# NFC_Card2.net
KiCad netlist of a schematic drawn in EasyEDA Pro
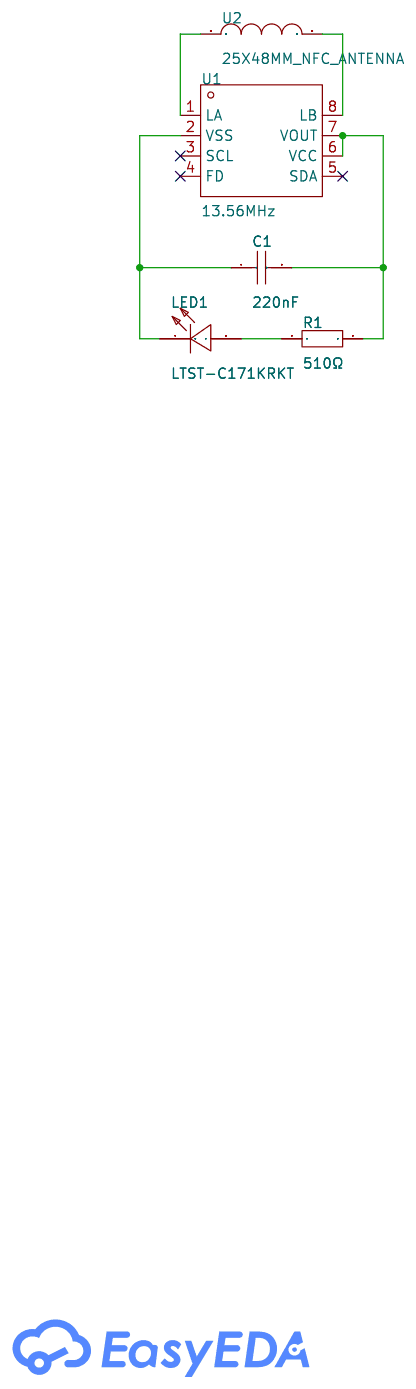
[diagram p0: schematic sheet]

(export (version "E")
  (design (tool "Eeschema 10.0.6"))
  (components
    (comp (ref "C1")
      (value "220nF")
      (footprint "easyedapro:C0603")
      (description "容值:220nF;精度:±10%;额定电压:25V;材质(温度系数):X7R;")
      (fields
        (field (name "Manufacturer Part") "CL10B224KA8NNNC")
        (field (name "Manufacturer") "SAMSUNG(三星)")
      )
      (libsource (lib "easyedapro") (part "CL10B224KA8NNNC"))
    )
    (comp (ref "LED1")
      (value "LTST-C171KRKT")
      (footprint "easyedapro:LED-SMD_L2.0-W1.25-RD_RED")
      (fields (field (name "Manufacturer") "LITEON(光宝)"))
      (libsource (lib "easyedapro") (part "LTST-C171KRKT"))
    )
    (comp (ref "R1")
      (value "510Ω")
      (footprint "easyedapro:R0402")
      (fields (field (name "Manufacturer Part") "RC0402FR-07510RL") (field (name "Manufacturer") "YAGEO(国巨)"))
      (libsource (lib "easyedapro") (part "RC0402FR-07510RL"))
    )
    (comp (ref "U1")
      (value "13.56MHz")
      (footprint "easyedapro:XQFN-8_L1.6-W1.6-P0.50-BL_NT3H2111W0FHKH")
      (fields (field (name "Manufacturer Part") "NT3H2111W0FHKH") (field (name "Manufacturer") "NXP(恩智浦)"))
      (libsource (lib "easyedapro") (part "NT3H2111W0FHKH"))
    )
    (comp (ref "U2")
      (value "25X48MM_NFC_ANTENNA")
      (footprint "easyedapro:25X48MM_NFC_ANTENNA")
      (libsource (lib "easyedapro") (part "25X48MM_NFC_ANTENNA"))
    )
  )
  (nets
    (net (code "1") (name "Net-(LED1-A)") (class "Default")
      (node (ref "LED1") (pin "2") (pinfunction "A_2") (pintype "input"))
      (node (ref "R1") (pin "1") (pinfunction "1_1") (pintype "unspecified"))
    )
    (net (code "2") (name "Net-(LED1-C)") (class "Default")
      (node (ref "C1") (pin "1") (pinfunction "1_1") (pintype "input"))
      (node (ref "LED1") (pin "1") (pinfunction "C_1") (pintype "input"))
      (node (ref "U1") (pin "2") (pinfunction "VSS_2") (pintype "unspecified"))
    )
    (net (code "3") (name "Net-(U1-LA)") (class "Default")
      (node (ref "U1") (pin "1") (pinfunction "LA_1") (pintype "unspecified"))
      (node (ref "U2") (pin "P$1") (pinfunction "P$1_P$1") (pintype "bidirectional"))
    )
    (net (code "4") (name "Net-(U1-LB)") (class "Default")
      (node (ref "U1") (pin "8") (pinfunction "LB_8") (pintype "unspecified"))
      (node (ref "U2") (pin "P$2") (pinfunction "P$2_P$2") (pintype "bidirectional"))
    )
    (net (code "5") (name "Net-(U1-VCC)") (class "Default")
      (node (ref "C1") (pin "2") (pinfunction "2_2") (pintype "input"))
      (node (ref "R1") (pin "2") (pinfunction "2_2") (pintype "unspecified"))
      (node (ref "U1") (pin "6") (pinfunction "VCC_6") (pintype "unspecified"))
      (node (ref "U1") (pin "7") (pinfunction "VOUT_7") (pintype "unspecified"))
    )
    (net (code "6") (name "unconnected-(U1-FD-Pad4)") (class "Default")
      (node (ref "U1") (pin "4") (pinfunction "FD_4") (pintype "unspecified+no_connect"))
    )
    (net (code "7") (name "unconnected-(U1-SCL-Pad3)") (class "Default")
      (node (ref "U1") (pin "3") (pinfunction "SCL_3") (pintype "unspecified+no_connect"))
    )
    (net (code "8") (name "unconnected-(U1-SDA-Pad5)") (class "Default")
      (node (ref "U1") (pin "5") (pinfunction "SDA_5") (pintype "unspecified+no_connect"))
    )
  )
)
